# Sheet1.net
KiCad netlist of a schematic drawn in Altium Designer
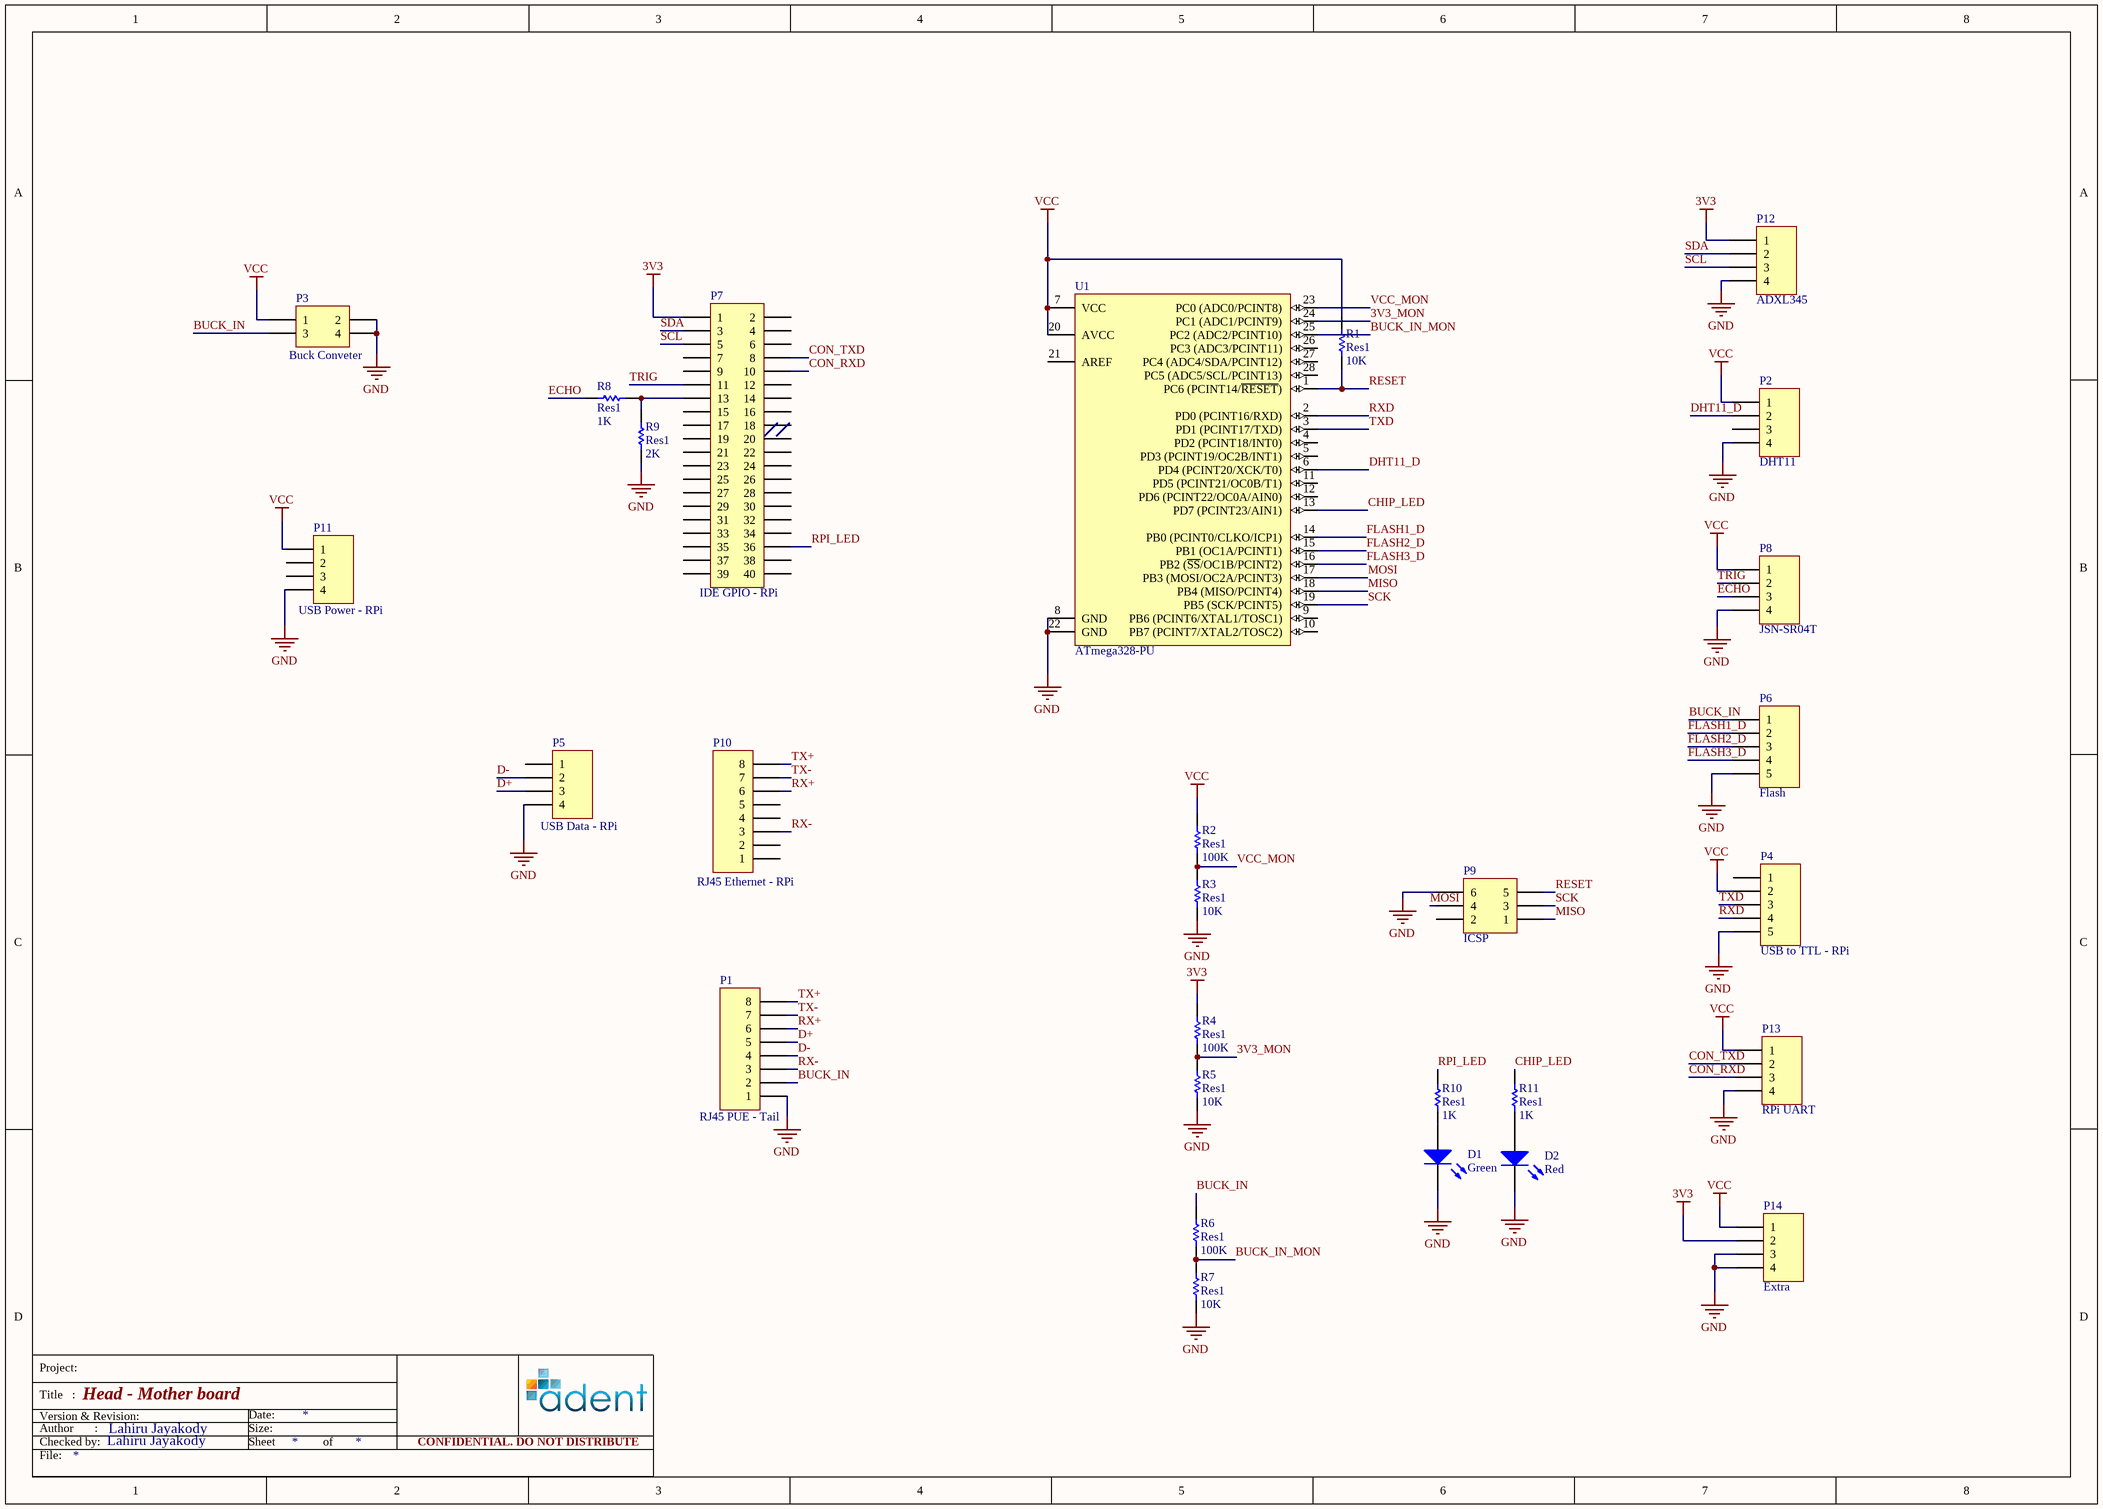
[diagram p0: Sheet1.SchDoc]

(export (version "E")
  (design (tool "Eeschema 10.0.6"))
  (components
    (comp (ref "D1")
      (value "Green")
      (footprint "LED-1")
      (description "Typical RED GaAs LED")
      (fields (field (name "PUBLISHER") "Altium Limited"))
      (libsource (lib "Miscellaneous Devices") (part "LED1"))
    )
    (comp (ref "D2")
      (value "Red")
      (footprint "LED-1")
      (description "Typical RED GaAs LED")
      (fields (field (name "PUBLISHER") "Altium Limited"))
      (libsource (lib "Miscellaneous Devices") (part "LED1"))
    )
    (comp (ref "P1")
      (value "RJ45 PUE - Tail")
      (footprint "RJ45")
      (description "Header, 8-Pin")
      (fields (field (name "PUBLISHER") "Altium Limited"))
      (libsource (lib "Miscellaneous Connectors") (part "Header 8"))
    )
    (comp (ref "P2")
      (value "DHT11")
      (footprint "HDR1X4")
      (description "Header, 4-Pin")
      (fields (field (name "PUBLISHER") "Altium Limited"))
      (libsource (lib "Miscellaneous Connectors") (part "Header 4"))
    )
    (comp (ref "P3")
      (value "Buck Conveter")
      (footprint "HDR2X2")
      (description "Header, 2-Pin, Dual row")
      (fields (field (name "PUBLISHER") "Altium Limited"))
      (libsource (lib "Miscellaneous Connectors") (part "Header 2X2"))
    )
    (comp (ref "P4")
      (value "USB to TTL - RPi")
      (footprint "HDR1X5")
      (description "Header, 5-Pin")
      (fields (field (name "PUBLISHER") "Altium Limited"))
      (libsource (lib "Miscellaneous Connectors") (part "Header 5"))
    )
    (comp (ref "P5")
      (value "USB Data - RPi")
      (footprint "USB_Female")
      (description "Header, 4-Pin")
      (fields (field (name "PUBLISHER") "Altium Limited"))
      (libsource (lib "Miscellaneous Connectors") (part "Header 4"))
    )
    (comp (ref "P6")
      (value "Flash")
      (footprint "HDR1X5")
      (description "Header, 5-Pin")
      (fields (field (name "PUBLISHER") "Altium Limited"))
      (libsource (lib "Miscellaneous Connectors") (part "Header 5"))
    )
    (comp (ref "P7")
      (value "IDE GPIO - RPi")
      (footprint "HDR2X20")
      (description "Header, 20-Pin, Dual row")
      (fields (field (name "PUBLISHER") "Altium Limited"))
      (libsource (lib "Miscellaneous Connectors") (part "Header 20X2"))
    )
    (comp (ref "P8")
      (value "JSN-SR04T")
      (footprint "HDR1X4")
      (description "Header, 4-Pin")
      (fields (field (name "PUBLISHER") "Altium Limited"))
      (libsource (lib "Miscellaneous Connectors") (part "Header 4"))
    )
    (comp (ref "P9")
      (value "ICSP")
      (footprint "HDR2X3")
      (description "Header, 3-Pin, Dual row")
      (fields (field (name "PUBLISHER") "Altium Limited"))
      (libsource (lib "Miscellaneous Connectors") (part "Header 3X2"))
    )
    (comp (ref "P10")
      (value "RJ45 Ethernet - RPi")
      (footprint "RJ45")
      (description "Header, 8-Pin")
      (fields (field (name "PUBLISHER") "Altium Limited"))
      (libsource (lib "Miscellaneous Connectors") (part "Header 8"))
    )
    (comp (ref "P11")
      (value "USB Power - RPi")
      (footprint "USB_Female")
      (description "Header, 4-Pin")
      (fields (field (name "PUBLISHER") "Altium Limited"))
      (libsource (lib "Miscellaneous Connectors") (part "Header 4"))
    )
    (comp (ref "P12")
      (value "ADXL345")
      (footprint "HDR1X4")
      (description "Header, 4-Pin")
      (fields (field (name "PUBLISHER") "Altium Limited"))
      (libsource (lib "Miscellaneous Connectors") (part "Header 4"))
    )
    (comp (ref "P13")
      (value "RPi UART")
      (footprint "HDR1X4")
      (description "Header, 4-Pin")
      (fields (field (name "PUBLISHER") "Altium Limited"))
      (libsource (lib "Miscellaneous Connectors") (part "Header 4"))
    )
    (comp (ref "P14")
      (value "Extra")
      (footprint "HDR1X4")
      (description "Header, 4-Pin")
      (fields (field (name "PUBLISHER") "Altium Limited"))
      (libsource (lib "Miscellaneous Connectors") (part "Header 4"))
    )
    (comp (ref "R1")
      (value "Res1")
      (footprint "AXIAL-0.3")
      (description "Resistor")
      (fields (field (name "ALTIUM_VALUE") "10K") (field (name "PUBLISHER") "Altium Limited"))
      (libsource (lib "Miscellaneous Devices") (part "Res1"))
    )
    (comp (ref "R2")
      (value "Res1")
      (footprint "AXIAL-0.3")
      (description "Resistor")
      (fields (field (name "ALTIUM_VALUE") "100K") (field (name "PUBLISHER") "Altium Limited"))
      (libsource (lib "Miscellaneous Devices") (part "Res1"))
    )
    (comp (ref "R3")
      (value "Res1")
      (footprint "AXIAL-0.3")
      (description "Resistor")
      (fields (field (name "ALTIUM_VALUE") "10K") (field (name "PUBLISHER") "Altium Limited"))
      (libsource (lib "Miscellaneous Devices") (part "Res1"))
    )
    (comp (ref "R4")
      (value "Res1")
      (footprint "AXIAL-0.3")
      (description "Resistor")
      (fields (field (name "ALTIUM_VALUE") "100K") (field (name "PUBLISHER") "Altium Limited"))
      (libsource (lib "Miscellaneous Devices") (part "Res1"))
    )
    (comp (ref "R5")
      (value "Res1")
      (footprint "AXIAL-0.3")
      (description "Resistor")
      (fields (field (name "ALTIUM_VALUE") "10K") (field (name "PUBLISHER") "Altium Limited"))
      (libsource (lib "Miscellaneous Devices") (part "Res1"))
    )
    (comp (ref "R6")
      (value "Res1")
      (footprint "AXIAL-0.3")
      (description "Resistor")
      (fields (field (name "ALTIUM_VALUE") "100K") (field (name "PUBLISHER") "Altium Limited"))
      (libsource (lib "Miscellaneous Devices") (part "Res1"))
    )
    (comp (ref "R7")
      (value "Res1")
      (footprint "AXIAL-0.3")
      (description "Resistor")
      (fields (field (name "ALTIUM_VALUE") "10K") (field (name "PUBLISHER") "Altium Limited"))
      (libsource (lib "Miscellaneous Devices") (part "Res1"))
    )
    (comp (ref "R8")
      (value "Res1")
      (footprint "AXIAL-0.3")
      (description "Resistor")
      (fields (field (name "ALTIUM_VALUE") "1K") (field (name "PUBLISHER") "Altium Limited"))
      (libsource (lib "Miscellaneous Devices") (part "Res1"))
    )
    (comp (ref "R9")
      (value "Res1")
      (footprint "AXIAL-0.3")
      (description "Resistor")
      (fields (field (name "ALTIUM_VALUE") "2K") (field (name "PUBLISHER") "Altium Limited"))
      (libsource (lib "Miscellaneous Devices") (part "Res1"))
    )
    (comp (ref "R10")
      (value "Res1")
      (footprint "AXIAL-0.3")
      (description "Resistor")
      (fields (field (name "ALTIUM_VALUE") "1K") (field (name "PUBLISHER") "Altium Limited"))
      (libsource (lib "Miscellaneous Devices") (part "Res1"))
    )
    (comp (ref "R11")
      (value "Res1")
      (footprint "AXIAL-0.3")
      (description "Resistor")
      (fields (field (name "ALTIUM_VALUE") "1K") (field (name "PUBLISHER") "Altium Limited"))
      (libsource (lib "Miscellaneous Devices") (part "Res1"))
    )
    (comp (ref "U1")
      (value "ATmega328-PU")
      (footprint "28P3")
      (fields (field (name "PUBLISHER") "Altium Limited"))
      (libsource (lib "Atmel Microcontroller 8-Bit megaAVR") (part "ATmega328-PU"))
    )
  )
  (nets
    (net (code "1") (name "/3V3_MON") (class "Default")
      (node (ref "R4") (pin "1") (pinfunction "1_1") (pintype "passive"))
      (node (ref "R5") (pin "2") (pinfunction "2_2") (pintype "passive"))
      (node (ref "U1") (pin "24") (pinfunction "PC1_(ADC1/PCINT9)_24") (pintype "bidirectional"))
    )
    (net (code "2") (name "/BUCK_IN") (class "Default")
      (node (ref "P1") (pin "2") (pinfunction "2_2") (pintype "passive"))
      (node (ref "P3") (pin "3") (pinfunction "3_3") (pintype "passive"))
      (node (ref "P6") (pin "1") (pinfunction "1_1") (pintype "passive"))
      (node (ref "R6") (pin "2") (pinfunction "2_2") (pintype "passive"))
    )
    (net (code "3") (name "/BUCK_IN_MON") (class "Default")
      (node (ref "R6") (pin "1") (pinfunction "1_1") (pintype "passive"))
      (node (ref "R7") (pin "2") (pinfunction "2_2") (pintype "passive"))
      (node (ref "U1") (pin "25") (pinfunction "PC2_(ADC2/PCINT10)_25") (pintype "bidirectional"))
    )
    (net (code "4") (name "/CHIP_LED") (class "Default")
      (node (ref "R11") (pin "2") (pinfunction "2_2") (pintype "passive"))
      (node (ref "U1") (pin "13") (pinfunction "PD7_(PCINT23/AIN1)_13") (pintype "bidirectional"))
    )
    (net (code "5") (name "/CON_RXD") (class "Default")
      (node (ref "P13") (pin "3") (pinfunction "3_3") (pintype "passive"))
      (node (ref "P7") (pin "10") (pinfunction "10_10") (pintype "passive"))
    )
    (net (code "6") (name "/CON_TXD") (class "Default")
      (node (ref "P13") (pin "2") (pinfunction "2_2") (pintype "passive"))
      (node (ref "P7") (pin "8") (pinfunction "8_8") (pintype "passive"))
    )
    (net (code "7") (name "/D+") (class "Default")
      (node (ref "P1") (pin "5") (pinfunction "5_5") (pintype "passive"))
      (node (ref "P5") (pin "3") (pinfunction "3_3") (pintype "passive"))
    )
    (net (code "8") (name "/D-") (class "Default")
      (node (ref "P1") (pin "4") (pinfunction "4_4") (pintype "passive"))
      (node (ref "P5") (pin "2") (pinfunction "2_2") (pintype "passive"))
    )
    (net (code "9") (name "/DHT11_D") (class "Default")
      (node (ref "P2") (pin "2") (pinfunction "2_2") (pintype "passive"))
      (node (ref "U1") (pin "6") (pinfunction "PD4_(PCINT20/XCK/T0)_6") (pintype "bidirectional"))
    )
    (net (code "10") (name "/ECHO") (class "Default")
      (node (ref "P8") (pin "3") (pinfunction "3_3") (pintype "passive"))
      (node (ref "R8") (pin "1") (pinfunction "1_1") (pintype "passive"))
    )
    (net (code "11") (name "/FLASH1_D") (class "Default")
      (node (ref "P6") (pin "2") (pinfunction "2_2") (pintype "passive"))
      (node (ref "U1") (pin "14") (pinfunction "PB0_(PCINT0/CLKO/ICP1)_14") (pintype "bidirectional"))
    )
    (net (code "12") (name "/FLASH2_D") (class "Default")
      (node (ref "P6") (pin "3") (pinfunction "3_3") (pintype "passive"))
      (node (ref "U1") (pin "15") (pinfunction "PB1_(OC1A/PCINT1)_15") (pintype "bidirectional"))
    )
    (net (code "13") (name "/FLASH3_D") (class "Default")
      (node (ref "P6") (pin "4") (pinfunction "4_4") (pintype "passive"))
      (node (ref "U1") (pin "16") (pinfunction "PB2_(~{SS}/OC1B/PCINT2)_16") (pintype "bidirectional"))
    )
    (net (code "14") (name "/MISO") (class "Default")
      (node (ref "P9") (pin "1") (pinfunction "1_1") (pintype "passive"))
      (node (ref "U1") (pin "18") (pinfunction "PB4_(MISO/PCINT4)_18") (pintype "bidirectional"))
    )
    (net (code "15") (name "/MOSI") (class "Default")
      (node (ref "P9") (pin "4") (pinfunction "4_4") (pintype "passive"))
      (node (ref "U1") (pin "17") (pinfunction "PB3_(MOSI/OC2A/PCINT3)_17") (pintype "bidirectional"))
    )
    (net (code "16") (name "/RESET") (class "Default")
      (node (ref "P9") (pin "5") (pinfunction "5_5") (pintype "passive"))
      (node (ref "R1") (pin "1") (pinfunction "1_1") (pintype "passive"))
      (node (ref "U1") (pin "1") (pinfunction "PC6_(PCINT14/~{RESET})_1") (pintype "bidirectional"))
    )
    (net (code "17") (name "/RPI_LED") (class "Default")
      (node (ref "P7") (pin "36") (pinfunction "36_36") (pintype "passive"))
      (node (ref "R10") (pin "2") (pinfunction "2_2") (pintype "passive"))
    )
    (net (code "18") (name "/RX+") (class "Default")
      (node (ref "P1") (pin "6") (pinfunction "6_6") (pintype "passive"))
      (node (ref "P10") (pin "6") (pinfunction "6_6") (pintype "passive"))
    )
    (net (code "19") (name "/RX-") (class "Default")
      (node (ref "P1") (pin "3") (pinfunction "3_3") (pintype "passive"))
      (node (ref "P10") (pin "3") (pinfunction "3_3") (pintype "passive"))
    )
    (net (code "20") (name "/RXD") (class "Default")
      (node (ref "P4") (pin "4") (pinfunction "4_4") (pintype "passive"))
      (node (ref "U1") (pin "2") (pinfunction "PD0_(PCINT16/RXD)_2") (pintype "bidirectional"))
    )
    (net (code "21") (name "/SCK") (class "Default")
      (node (ref "P9") (pin "3") (pinfunction "3_3") (pintype "passive"))
      (node (ref "U1") (pin "19") (pinfunction "PB5_(SCK/PCINT5)_19") (pintype "bidirectional"))
    )
    (net (code "22") (name "/SCL") (class "Default")
      (node (ref "P12") (pin "3") (pinfunction "3_3") (pintype "passive"))
      (node (ref "P7") (pin "5") (pinfunction "5_5") (pintype "passive"))
    )
    (net (code "23") (name "/SDA") (class "Default")
      (node (ref "P12") (pin "2") (pinfunction "2_2") (pintype "passive"))
      (node (ref "P7") (pin "3") (pinfunction "3_3") (pintype "passive"))
    )
    (net (code "24") (name "/TRIG") (class "Default")
      (node (ref "P7") (pin "11") (pinfunction "11_11") (pintype "passive"))
      (node (ref "P8") (pin "2") (pinfunction "2_2") (pintype "passive"))
    )
    (net (code "25") (name "/TX+") (class "Default")
      (node (ref "P1") (pin "8") (pinfunction "8_8") (pintype "passive"))
      (node (ref "P10") (pin "8") (pinfunction "8_8") (pintype "passive"))
    )
    (net (code "26") (name "/TX-") (class "Default")
      (node (ref "P1") (pin "7") (pinfunction "7_7") (pintype "passive"))
      (node (ref "P10") (pin "7") (pinfunction "7_7") (pintype "passive"))
    )
    (net (code "27") (name "/TXD") (class "Default")
      (node (ref "P4") (pin "3") (pinfunction "3_3") (pintype "passive"))
      (node (ref "U1") (pin "3") (pinfunction "PD1_(PCINT17/TXD)_3") (pintype "bidirectional"))
    )
    (net (code "28") (name "/VCC_MON") (class "Default")
      (node (ref "R2") (pin "1") (pinfunction "1_1") (pintype "passive"))
      (node (ref "R3") (pin "2") (pinfunction "2_2") (pintype "passive"))
      (node (ref "U1") (pin "23") (pinfunction "PC0_(ADC0/PCINT8)_23") (pintype "bidirectional"))
    )
    (net (code "29") (name "3V3") (class "Default")
      (node (ref "P12") (pin "1") (pinfunction "1_1") (pintype "passive"))
      (node (ref "P14") (pin "2") (pinfunction "2_2") (pintype "passive"))
      (node (ref "P7") (pin "1") (pinfunction "1_1") (pintype "passive"))
      (node (ref "R4") (pin "2") (pinfunction "2_2") (pintype "passive"))
    )
    (net (code "30") (name "GND") (class "Default")
      (node (ref "D1") (pin "2") (pinfunction "K_2") (pintype "passive"))
      (node (ref "D2") (pin "2") (pinfunction "K_2") (pintype "passive"))
      (node (ref "P1") (pin "1") (pinfunction "1_1") (pintype "passive"))
      (node (ref "P11") (pin "4") (pinfunction "4_4") (pintype "passive"))
      (node (ref "P12") (pin "4") (pinfunction "4_4") (pintype "passive"))
      (node (ref "P13") (pin "4") (pinfunction "4_4") (pintype "passive"))
      (node (ref "P14") (pin "3") (pinfunction "3_3") (pintype "passive"))
      (node (ref "P14") (pin "4") (pinfunction "4_4") (pintype "passive"))
      (node (ref "P2") (pin "4") (pinfunction "4_4") (pintype "passive"))
      (node (ref "P3") (pin "2") (pinfunction "2_2") (pintype "passive"))
      (node (ref "P3") (pin "4") (pinfunction "4_4") (pintype "passive"))
      (node (ref "P4") (pin "5") (pinfunction "5_5") (pintype "passive"))
      (node (ref "P5") (pin "4") (pinfunction "4_4") (pintype "passive"))
      (node (ref "P6") (pin "5") (pinfunction "5_5") (pintype "passive"))
      (node (ref "P8") (pin "4") (pinfunction "4_4") (pintype "passive"))
      (node (ref "P9") (pin "6") (pinfunction "6_6") (pintype "passive"))
      (node (ref "R3") (pin "1") (pinfunction "1_1") (pintype "passive"))
      (node (ref "R5") (pin "1") (pinfunction "1_1") (pintype "passive"))
      (node (ref "R7") (pin "1") (pinfunction "1_1") (pintype "passive"))
      (node (ref "R9") (pin "1") (pinfunction "1_1") (pintype "passive"))
      (node (ref "U1") (pin "22") (pinfunction "GND_22") (pintype "power_in"))
      (node (ref "U1") (pin "8") (pinfunction "GND_8") (pintype "power_in"))
    )
    (net (code "31") (name "Net-(D1-A)") (class "Default")
      (node (ref "D1") (pin "1") (pinfunction "A_1") (pintype "passive"))
      (node (ref "R10") (pin "1") (pinfunction "1_1") (pintype "passive"))
    )
    (net (code "32") (name "Net-(D2-A)") (class "Default")
      (node (ref "D2") (pin "1") (pinfunction "A_1") (pintype "passive"))
      (node (ref "R11") (pin "1") (pinfunction "1_1") (pintype "passive"))
    )
    (net (code "33") (name "Net-(P7-Pad13)") (class "Default")
      (node (ref "P7") (pin "13") (pinfunction "13_13") (pintype "passive"))
      (node (ref "R8") (pin "2") (pinfunction "2_2") (pintype "passive"))
      (node (ref "R9") (pin "2") (pinfunction "2_2") (pintype "passive"))
    )
    (net (code "34") (name "VCC") (class "Default")
      (node (ref "P11") (pin "1") (pinfunction "1_1") (pintype "passive"))
      (node (ref "P13") (pin "1") (pinfunction "1_1") (pintype "passive"))
      (node (ref "P14") (pin "1") (pinfunction "1_1") (pintype "passive"))
      (node (ref "P2") (pin "1") (pinfunction "1_1") (pintype "passive"))
      (node (ref "P3") (pin "1") (pinfunction "1_1") (pintype "passive"))
      (node (ref "P4") (pin "2") (pinfunction "2_2") (pintype "passive"))
      (node (ref "P8") (pin "1") (pinfunction "1_1") (pintype "passive"))
      (node (ref "R1") (pin "2") (pinfunction "2_2") (pintype "passive"))
      (node (ref "R2") (pin "2") (pinfunction "2_2") (pintype "passive"))
      (node (ref "U1") (pin "20") (pinfunction "AVCC_20") (pintype "power_in"))
      (node (ref "U1") (pin "7") (pinfunction "VCC_7") (pintype "power_in"))
    )
    (net (code "35") (name "unconnected-(P2-Pad3)") (class "Default")
      (node (ref "P2") (pin "3") (pinfunction "3_3") (pintype "passive"))
    )
    (net (code "36") (name "unconnected-(P4-Pad1)") (class "Default")
      (node (ref "P4") (pin "1") (pinfunction "1_1") (pintype "passive"))
    )
    (net (code "37") (name "unconnected-(P5-Pad1)") (class "Default")
      (node (ref "P5") (pin "1") (pinfunction "1_1") (pintype "passive"))
    )
    (net (code "38") (name "unconnected-(P7-Pad2)") (class "Default")
      (node (ref "P7") (pin "2") (pinfunction "2_2") (pintype "passive"))
    )
    (net (code "39") (name "unconnected-(P7-Pad4)") (class "Default")
      (node (ref "P7") (pin "4") (pinfunction "4_4") (pintype "passive"))
    )
    (net (code "40") (name "unconnected-(P7-Pad6)") (class "Default")
      (node (ref "P7") (pin "6") (pinfunction "6_6") (pintype "passive"))
    )
    (net (code "41") (name "unconnected-(P7-Pad7)") (class "Default")
      (node (ref "P7") (pin "7") (pinfunction "7_7") (pintype "passive"))
    )
    (net (code "42") (name "unconnected-(P7-Pad9)") (class "Default")
      (node (ref "P7") (pin "9") (pinfunction "9_9") (pintype "passive"))
    )
    (net (code "43") (name "unconnected-(P7-Pad12)") (class "Default")
      (node (ref "P7") (pin "12") (pinfunction "12_12") (pintype "passive"))
    )
    (net (code "44") (name "unconnected-(P7-Pad14)") (class "Default")
      (node (ref "P7") (pin "14") (pinfunction "14_14") (pintype "passive"))
    )
    (net (code "45") (name "unconnected-(P7-Pad15)") (class "Default")
      (node (ref "P7") (pin "15") (pinfunction "15_15") (pintype "passive"))
    )
    (net (code "46") (name "unconnected-(P7-Pad16)") (class "Default")
      (node (ref "P7") (pin "16") (pinfunction "16_16") (pintype "passive"))
    )
    (net (code "47") (name "unconnected-(P7-Pad17)") (class "Default")
      (node (ref "P7") (pin "17") (pinfunction "17_17") (pintype "passive"))
    )
    (net (code "48") (name "unconnected-(P7-Pad18)") (class "Default")
      (node (ref "P7") (pin "18") (pinfunction "18_18") (pintype "passive"))
    )
    (net (code "49") (name "unconnected-(P7-Pad19)") (class "Default")
      (node (ref "P7") (pin "19") (pinfunction "19_19") (pintype "passive"))
    )
    (net (code "50") (name "unconnected-(P7-Pad20)") (class "Default")
      (node (ref "P7") (pin "20") (pinfunction "20_20") (pintype "passive"))
    )
    (net (code "51") (name "unconnected-(P7-Pad21)") (class "Default")
      (node (ref "P7") (pin "21") (pinfunction "21_21") (pintype "passive"))
    )
    (net (code "52") (name "unconnected-(P7-Pad22)") (class "Default")
      (node (ref "P7") (pin "22") (pinfunction "22_22") (pintype "passive"))
    )
    (net (code "53") (name "unconnected-(P7-Pad23)") (class "Default")
      (node (ref "P7") (pin "23") (pinfunction "23_23") (pintype "passive"))
    )
    (net (code "54") (name "unconnected-(P7-Pad24)") (class "Default")
      (node (ref "P7") (pin "24") (pinfunction "24_24") (pintype "passive"))
    )
    (net (code "55") (name "unconnected-(P7-Pad25)") (class "Default")
      (node (ref "P7") (pin "25") (pinfunction "25_25") (pintype "passive"))
    )
    (net (code "56") (name "unconnected-(P7-Pad26)") (class "Default")
      (node (ref "P7") (pin "26") (pinfunction "26_26") (pintype "passive"))
    )
    (net (code "57") (name "unconnected-(P7-Pad27)") (class "Default")
      (node (ref "P7") (pin "27") (pinfunction "27_27") (pintype "passive"))
    )
    (net (code "58") (name "unconnected-(P7-Pad28)") (class "Default")
      (node (ref "P7") (pin "28") (pinfunction "28_28") (pintype "passive"))
    )
    (net (code "59") (name "unconnected-(P7-Pad29)") (class "Default")
      (node (ref "P7") (pin "29") (pinfunction "29_29") (pintype "passive"))
    )
    (net (code "60") (name "unconnected-(P7-Pad30)") (class "Default")
      (node (ref "P7") (pin "30") (pinfunction "30_30") (pintype "passive"))
    )
    (net (code "61") (name "unconnected-(P7-Pad31)") (class "Default")
      (node (ref "P7") (pin "31") (pinfunction "31_31") (pintype "passive"))
    )
    (net (code "62") (name "unconnected-(P7-Pad32)") (class "Default")
      (node (ref "P7") (pin "32") (pinfunction "32_32") (pintype "passive"))
    )
    (net (code "63") (name "unconnected-(P7-Pad33)") (class "Default")
      (node (ref "P7") (pin "33") (pinfunction "33_33") (pintype "passive"))
    )
    (net (code "64") (name "unconnected-(P7-Pad34)") (class "Default")
      (node (ref "P7") (pin "34") (pinfunction "34_34") (pintype "passive"))
    )
    (net (code "65") (name "unconnected-(P7-Pad35)") (class "Default")
      (node (ref "P7") (pin "35") (pinfunction "35_35") (pintype "passive"))
    )
    (net (code "66") (name "unconnected-(P7-Pad37)") (class "Default")
      (node (ref "P7") (pin "37") (pinfunction "37_37") (pintype "passive"))
    )
    (net (code "67") (name "unconnected-(P7-Pad38)") (class "Default")
      (node (ref "P7") (pin "38") (pinfunction "38_38") (pintype "passive"))
    )
    (net (code "68") (name "unconnected-(P7-Pad39)") (class "Default")
      (node (ref "P7") (pin "39") (pinfunction "39_39") (pintype "passive"))
    )
    (net (code "69") (name "unconnected-(P7-Pad40)") (class "Default")
      (node (ref "P7") (pin "40") (pinfunction "40_40") (pintype "passive"))
    )
    (net (code "70") (name "unconnected-(P9-Pad2)") (class "Default")
      (node (ref "P9") (pin "2") (pinfunction "2_2") (pintype "passive"))
    )
    (net (code "71") (name "unconnected-(P10-Pad1)") (class "Default")
      (node (ref "P10") (pin "1") (pinfunction "1_1") (pintype "passive"))
    )
    (net (code "72") (name "unconnected-(P10-Pad2)") (class "Default")
      (node (ref "P10") (pin "2") (pinfunction "2_2") (pintype "passive"))
    )
    (net (code "73") (name "unconnected-(P10-Pad4)") (class "Default")
      (node (ref "P10") (pin "4") (pinfunction "4_4") (pintype "passive"))
    )
    (net (code "74") (name "unconnected-(P10-Pad5)") (class "Default")
      (node (ref "P10") (pin "5") (pinfunction "5_5") (pintype "passive"))
    )
    (net (code "75") (name "unconnected-(P11-Pad2)") (class "Default")
      (node (ref "P11") (pin "2") (pinfunction "2_2") (pintype "passive"))
    )
    (net (code "76") (name "unconnected-(P11-Pad3)") (class "Default")
      (node (ref "P11") (pin "3") (pinfunction "3_3") (pintype "passive"))
    )
    (net (code "77") (name "unconnected-(U1-AREF-Pad21)") (class "Default")
      (node (ref "U1") (pin "21") (pinfunction "AREF_21") (pintype "power_in"))
    )
    (net (code "78") (name "unconnected-(U1-PB6_(PCINT6{slash}XTAL1{slash}TOSC1)-Pad9)") (class "Default")
      (node (ref "U1") (pin "9") (pinfunction "PB6_(PCINT6/XTAL1/TOSC1)_9") (pintype "bidirectional"))
    )
    (net (code "79") (name "unconnected-(U1-PB7_(PCINT7{slash}XTAL2{slash}TOSC2)-Pad10)") (class "Default")
      (node (ref "U1") (pin "10") (pinfunction "PB7_(PCINT7/XTAL2/TOSC2)_10") (pintype "bidirectional"))
    )
    (net (code "80") (name "unconnected-(U1-PC3_(ADC3{slash}PCINT11)-Pad26)") (class "Default")
      (node (ref "U1") (pin "26") (pinfunction "PC3_(ADC3/PCINT11)_26") (pintype "bidirectional"))
    )
    (net (code "81") (name "unconnected-(U1-PC4_(ADC4{slash}SDA{slash}PCINT12)-Pad27)") (class "Default")
      (node (ref "U1") (pin "27") (pinfunction "PC4_(ADC4/SDA/PCINT12)_27") (pintype "bidirectional"))
    )
    (net (code "82") (name "unconnected-(U1-PC5_(ADC5{slash}SCL{slash}PCINT13)-Pad28)") (class "Default")
      (node (ref "U1") (pin "28") (pinfunction "PC5_(ADC5/SCL/PCINT13)_28") (pintype "bidirectional"))
    )
    (net (code "83") (name "unconnected-(U1-PD2_(PCINT18{slash}INT0)-Pad4)") (class "Default")
      (node (ref "U1") (pin "4") (pinfunction "PD2_(PCINT18/INT0)_4") (pintype "bidirectional"))
    )
    (net (code "84") (name "unconnected-(U1-PD3_(PCINT19{slash}OC2B{slash}INT1)-Pad5)") (class "Default")
      (node (ref "U1") (pin "5") (pinfunction "PD3_(PCINT19/OC2B/INT1)_5") (pintype "bidirectional"))
    )
    (net (code "85") (name "unconnected-(U1-PD5_(PCINT21{slash}OC0B{slash}T1)-Pad11)") (class "Default")
      (node (ref "U1") (pin "11") (pinfunction "PD5_(PCINT21/OC0B/T1)_11") (pintype "bidirectional"))
    )
    (net (code "86") (name "unconnected-(U1-PD6_(PCINT22{slash}OC0A{slash}AIN0)-Pad12)") (class "Default")
      (node (ref "U1") (pin "12") (pinfunction "PD6_(PCINT22/OC0A/AIN0)_12") (pintype "bidirectional"))
    )
  )
)
